# Logique_Prio_Alim.net
KiCad netlist of a schematic drawn in Altium Designer
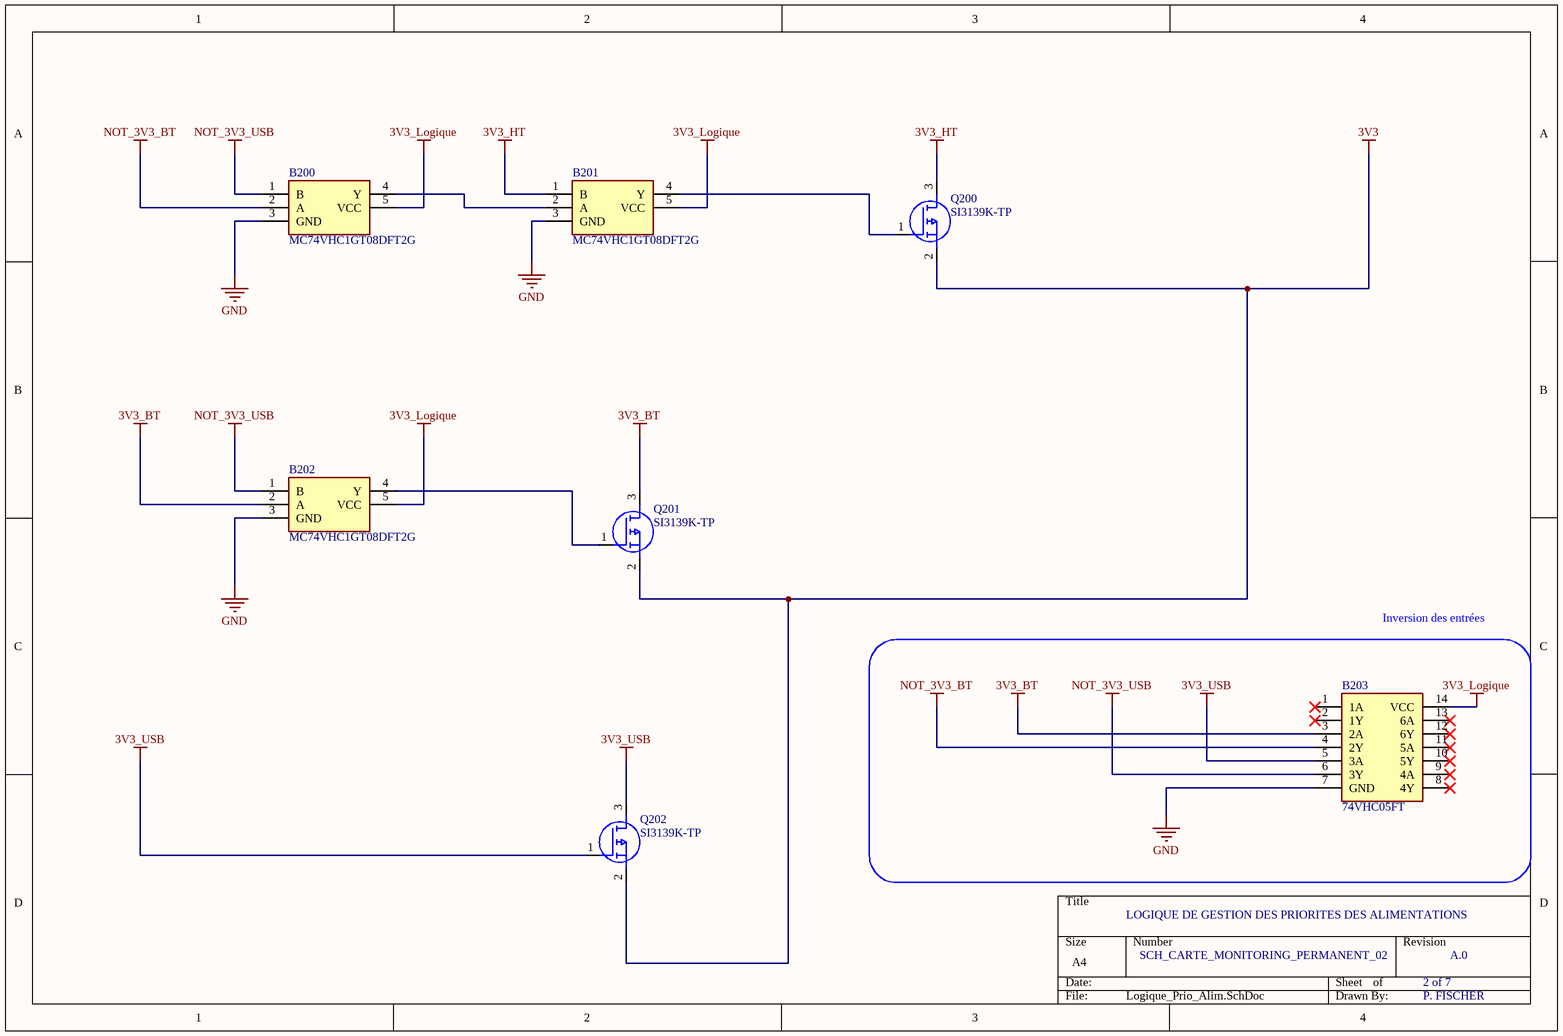
[diagram p0: Logique_Prio_Alim.SchDoc]

(export (version "E")
  (design (tool "Eeschema 10.0.6"))
  (components
    (comp (ref "B200")
      (value "MC74VHC1GT08DFT2G")
      (footprint "SOT65P210X110-5N")
      (description "Single 2-Input AND Gate, TTL Level")
      (libsource (lib "SCHLibrary") (part "MC74VHC1GT08DFT2G"))
    )
    (comp (ref "B201")
      (value "MC74VHC1GT08DFT2G")
      (footprint "SOT65P210X110-5N")
      (description "Single 2-Input AND Gate, TTL Level")
      (libsource (lib "SCHLibrary") (part "MC74VHC1GT08DFT2G"))
    )
    (comp (ref "B202")
      (value "MC74VHC1GT08DFT2G")
      (footprint "SOT65P210X110-5N")
      (description "Single 2-Input AND Gate, TTL Level")
      (libsource (lib "SCHLibrary") (part "MC74VHC1GT08DFT2G"))
    )
    (comp (ref "B203")
      (value "74VHC05FT")
      (footprint "SOP65P640X120-14N")
      (description "Logic Gates CMOS LOGIC IC INVERTER")
      (fields (field (name "MOUSER PART NUMBER") "757-74VHC05FT"))
      (libsource (lib "SCHLibrary") (part "74VHC05FT"))
    )
    (comp (ref "Q200")
      (value "SI3139K-TP")
      (footprint "SI3139K-TP")
      (description "MOSFET P-Channel MOSFET")
      (libsource (lib "SCHLibrary") (part "SI3139K-TP"))
    )
    (comp (ref "Q201")
      (value "SI3139K-TP")
      (footprint "SI3139K-TP")
      (description "MOSFET P-Channel MOSFET")
      (libsource (lib "SCHLibrary") (part "SI3139K-TP"))
    )
    (comp (ref "Q202")
      (value "SI3139K-TP")
      (footprint "SI3139K-TP")
      (description "MOSFET P-Channel MOSFET")
      (libsource (lib "SCHLibrary") (part "SI3139K-TP"))
    )
  )
  (nets
    (net (code "1") (name "3V3") (class "Default")
      (node (ref "Q200") (pin "2") (pinfunction "S_2") (pintype "passive"))
      (node (ref "Q201") (pin "2") (pinfunction "S_2") (pintype "passive"))
      (node (ref "Q202") (pin "2") (pinfunction "S_2") (pintype "passive"))
    )
    (net (code "2") (name "3V3_BT") (class "Default")
      (node (ref "B202") (pin "2") (pinfunction "A_2") (pintype "passive"))
      (node (ref "B203") (pin "3") (pinfunction "2A_3") (pintype "passive"))
      (node (ref "Q201") (pin "3") (pinfunction "D_3") (pintype "passive"))
    )
    (net (code "3") (name "3V3_HT") (class "Default")
      (node (ref "B201") (pin "1") (pinfunction "B_1") (pintype "passive"))
      (node (ref "Q200") (pin "3") (pinfunction "D_3") (pintype "passive"))
    )
    (net (code "4") (name "3V3_Logique") (class "Default")
      (node (ref "B200") (pin "5") (pinfunction "VCC_5") (pintype "passive"))
      (node (ref "B201") (pin "5") (pinfunction "VCC_5") (pintype "passive"))
      (node (ref "B202") (pin "5") (pinfunction "VCC_5") (pintype "passive"))
      (node (ref "B203") (pin "14") (pinfunction "VCC_14") (pintype "passive"))
    )
    (net (code "5") (name "3V3_USB") (class "Default")
      (node (ref "B203") (pin "5") (pinfunction "3A_5") (pintype "passive"))
      (node (ref "Q202") (pin "1") (pinfunction "G_1") (pintype "passive"))
      (node (ref "Q202") (pin "3") (pinfunction "D_3") (pintype "passive"))
    )
    (net (code "6") (name "GND") (class "Default")
      (node (ref "B200") (pin "3") (pinfunction "GND_3") (pintype "passive"))
      (node (ref "B201") (pin "3") (pinfunction "GND_3") (pintype "passive"))
      (node (ref "B202") (pin "3") (pinfunction "GND_3") (pintype "passive"))
      (node (ref "B203") (pin "7") (pinfunction "GND_7") (pintype "passive"))
    )
    (net (code "7") (name "NOT_3V3_BT") (class "Default")
      (node (ref "B200") (pin "2") (pinfunction "A_2") (pintype "passive"))
      (node (ref "B203") (pin "4") (pinfunction "2Y_4") (pintype "passive"))
    )
    (net (code "8") (name "NOT_3V3_USB") (class "Default")
      (node (ref "B200") (pin "1") (pinfunction "B_1") (pintype "passive"))
      (node (ref "B202") (pin "1") (pinfunction "B_1") (pintype "passive"))
      (node (ref "B203") (pin "6") (pinfunction "3Y_6") (pintype "passive"))
    )
    (net (code "9") (name "Net-(B200-Y)") (class "Default")
      (node (ref "B200") (pin "4") (pinfunction "Y_4") (pintype "passive"))
      (node (ref "B201") (pin "2") (pinfunction "A_2") (pintype "passive"))
    )
    (net (code "10") (name "Net-(B201-Y)") (class "Default")
      (node (ref "B201") (pin "4") (pinfunction "Y_4") (pintype "passive"))
      (node (ref "Q200") (pin "1") (pinfunction "G_1") (pintype "passive"))
    )
    (net (code "11") (name "Net-(B202-Y)") (class "Default")
      (node (ref "B202") (pin "4") (pinfunction "Y_4") (pintype "passive"))
      (node (ref "Q201") (pin "1") (pinfunction "G_1") (pintype "passive"))
    )
    (net (code "12") (name "unconnected-(B203-1A-Pad1)") (class "Default")
      (node (ref "B203") (pin "1") (pinfunction "1A_1") (pintype "passive+no_connect"))
    )
    (net (code "13") (name "unconnected-(B203-1Y-Pad2)") (class "Default")
      (node (ref "B203") (pin "2") (pinfunction "1Y_2") (pintype "passive+no_connect"))
    )
    (net (code "14") (name "unconnected-(B203-4A-Pad9)") (class "Default")
      (node (ref "B203") (pin "9") (pinfunction "4A_9") (pintype "passive+no_connect"))
    )
    (net (code "15") (name "unconnected-(B203-4Y-Pad8)") (class "Default")
      (node (ref "B203") (pin "8") (pinfunction "4Y_8") (pintype "passive+no_connect"))
    )
    (net (code "16") (name "unconnected-(B203-5A-Pad11)") (class "Default")
      (node (ref "B203") (pin "11") (pinfunction "5A_11") (pintype "passive+no_connect"))
    )
    (net (code "17") (name "unconnected-(B203-5Y-Pad10)") (class "Default")
      (node (ref "B203") (pin "10") (pinfunction "5Y_10") (pintype "passive+no_connect"))
    )
    (net (code "18") (name "unconnected-(B203-6A-Pad13)") (class "Default")
      (node (ref "B203") (pin "13") (pinfunction "6A_13") (pintype "passive+no_connect"))
    )
    (net (code "19") (name "unconnected-(B203-6Y-Pad12)") (class "Default")
      (node (ref "B203") (pin "12") (pinfunction "6Y_12") (pintype "passive+no_connect"))
    )
  )
)
